# PIC.net
KiCad netlist of a schematic drawn in Altium Designer
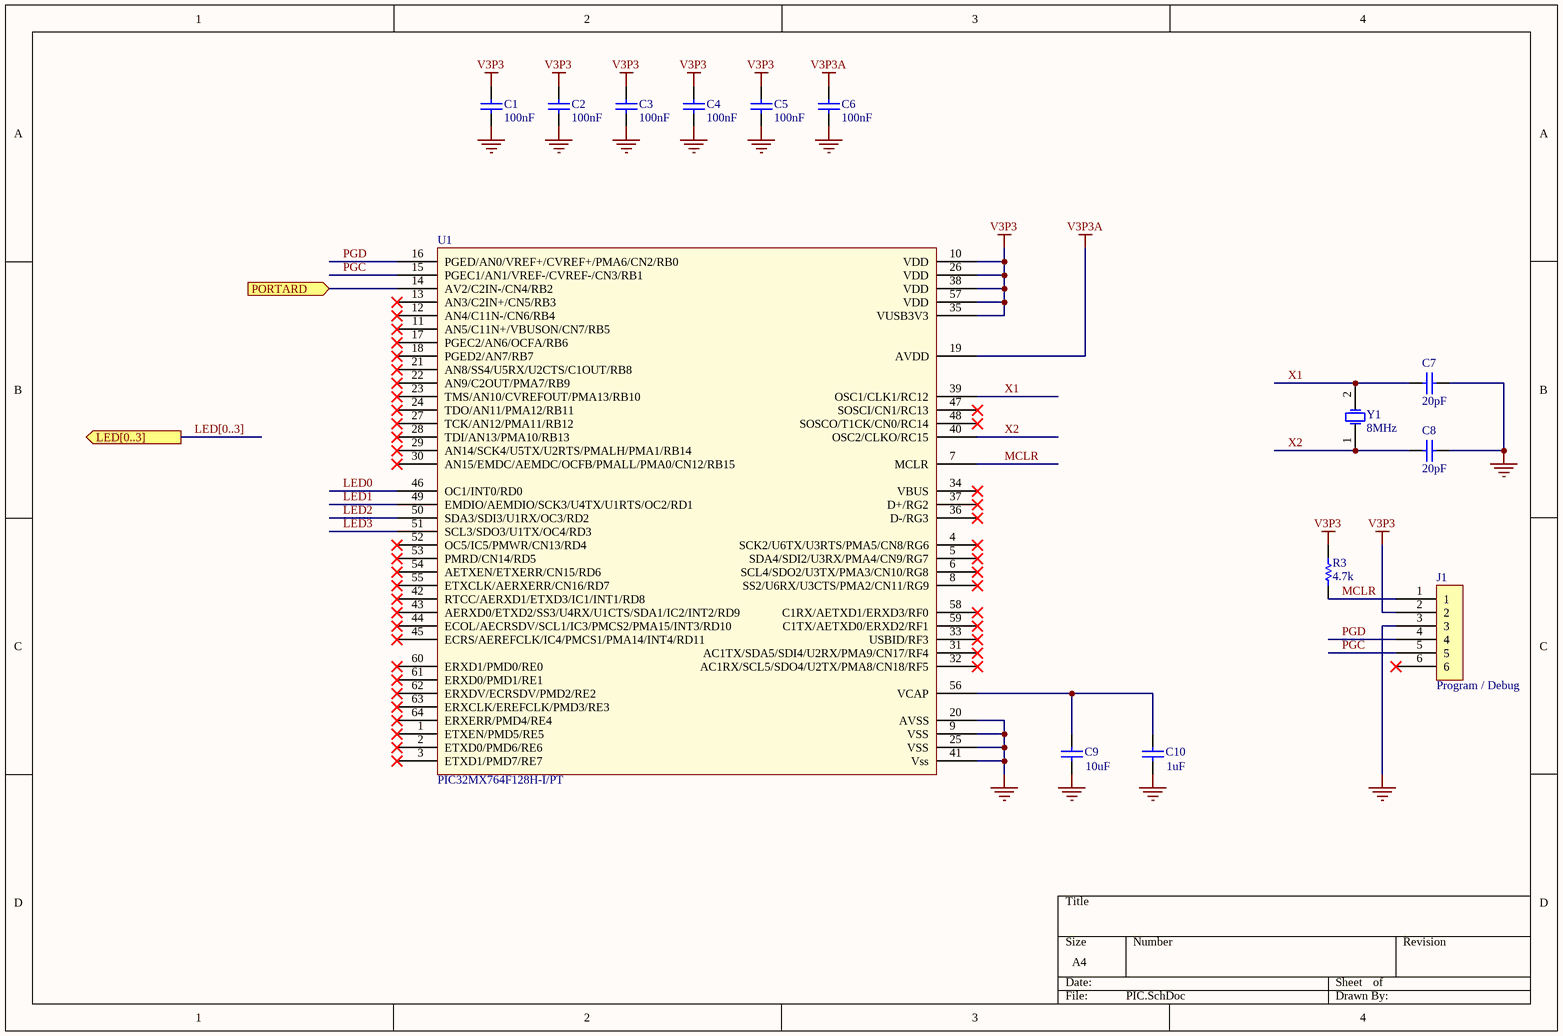
[diagram p0: PIC.SchDoc]

(export (version "E")
  (design (tool "Eeschema 10.0.6"))
  (components
    (comp (ref "C1")
      (value "100nF")
      (footprint "CAPC1608N")
      (description "Capacitor")
      (libsource (lib "Miscellaneous Devices") (part "Cap"))
    )
    (comp (ref "C2")
      (value "100nF")
      (footprint "CAPC1608N")
      (description "Capacitor")
      (libsource (lib "Miscellaneous Devices") (part "Cap"))
    )
    (comp (ref "C3")
      (value "100nF")
      (footprint "CAPC1608N")
      (description "Capacitor")
      (libsource (lib "Miscellaneous Devices") (part "Cap"))
    )
    (comp (ref "C4")
      (value "100nF")
      (footprint "CAPC1608N")
      (description "Capacitor")
      (libsource (lib "Miscellaneous Devices") (part "Cap"))
    )
    (comp (ref "C5")
      (value "100nF")
      (footprint "CAPC1608N")
      (description "Capacitor")
      (libsource (lib "Miscellaneous Devices") (part "Cap"))
    )
    (comp (ref "C6")
      (value "100nF")
      (footprint "CAPC1608N")
      (description "Capacitor")
      (libsource (lib "Miscellaneous Devices") (part "Cap"))
    )
    (comp (ref "C7")
      (value "20pF")
      (footprint "CAPC1608N")
      (description "Capacitor")
      (libsource (lib "Miscellaneous Devices") (part "Cap"))
    )
    (comp (ref "C8")
      (value "20pF")
      (footprint "CAPC1608N")
      (description "Capacitor")
      (libsource (lib "Miscellaneous Devices") (part "Cap"))
    )
    (comp (ref "C9")
      (value "10uF")
      (footprint "CAPC2012N")
      (description "Capacitor")
      (libsource (lib "Miscellaneous Devices") (part "Cap"))
    )
    (comp (ref "C10")
      (value "1uF")
      (footprint "CAPC1608N")
      (description "Capacitor")
      (libsource (lib "Miscellaneous Devices") (part "Cap"))
    )
    (comp (ref "J1")
      (value "Program / Debug")
      (footprint "RJ12_90")
      (libsource (lib "Schlib1") (part "Program / Debug"))
    )
    (comp (ref "R3")
      (value "4.7k")
      (footprint "RESC1608N")
      (description "Resistor")
      (libsource (lib "Miscellaneous Devices") (part "Res1"))
    )
    (comp (ref "U1")
      (value "PIC32MX764F128H-I/PT")
      (footprint "QFP50P1200X1200X120-64")
      (libsource (lib "Schlib1") (part "PIC32MX764F128H-I/PT"))
    )
    (comp (ref "Y1")
      (value "8MHz")
      (footprint "HC49/4H SMX Crystal")
      (description "Crystal Oscillator")
      (libsource (lib "Miscellaneous Devices") (part "XTAL"))
    )
  )
  (nets
    (net (code "1") (name "/LED0") (class "Default")
      (node (ref "U1") (pin "46") (pinfunction "OC1/INT0/RD0_46") (pintype "passive"))
    )
    (net (code "2") (name "/LED1") (class "Default")
      (node (ref "U1") (pin "49") (pinfunction "EMDIO/AEMDIO/SCK3/U4TX/U1RTS/OC2/RD1_49") (pintype "passive"))
    )
    (net (code "3") (name "/LED2") (class "Default")
      (node (ref "U1") (pin "50") (pinfunction "SDA3/SDI3/U1RX/OC3/RD2_50") (pintype "passive"))
    )
    (net (code "4") (name "/LED3") (class "Default")
      (node (ref "U1") (pin "51") (pinfunction "SCL3/SDO3/U1TX/OC4/RD3_51") (pintype "passive"))
    )
    (net (code "6") (name "/MCLR") (class "Default")
      (node (ref "J1") (pin "1") (pinfunction "1_1") (pintype "passive"))
      (node (ref "R3") (pin "1") (pinfunction "1_1") (pintype "passive"))
      (node (ref "U1") (pin "7") (pinfunction "MCLR_7") (pintype "passive"))
    )
    (net (code "7") (name "/PGC") (class "Default")
      (node (ref "J1") (pin "5") (pinfunction "5_5") (pintype "passive"))
      (node (ref "U1") (pin "15") (pinfunction "PGEC1/AN1/VREF-/CVREF-/CN3/RB1_15") (pintype "passive"))
    )
    (net (code "8") (name "/PGD") (class "Default")
      (node (ref "J1") (pin "4") (pinfunction "4_4") (pintype "passive"))
      (node (ref "U1") (pin "16") (pinfunction "PGED/AN0/VREF+/CVREF+/PMA6/CN2/RB0_16") (pintype "passive"))
    )
    (net (code "9") (name "/PORTARD") (class "Default")
      (node (ref "U1") (pin "14") (pinfunction "AV2/C2IN-/CN4/RB2_14") (pintype "passive"))
    )
    (net (code "10") (name "/X1") (class "Default")
      (node (ref "C7") (pin "1") (pinfunction "1_1") (pintype "passive"))
      (node (ref "U1") (pin "39") (pinfunction "OSC1/CLK1/RC12_39") (pintype "passive"))
      (node (ref "Y1") (pin "2") (pinfunction "OSC2_2") (pintype "passive"))
    )
    (net (code "11") (name "/X2") (class "Default")
      (node (ref "C8") (pin "1") (pinfunction "1_1") (pintype "passive"))
      (node (ref "U1") (pin "40") (pinfunction "OSC2/CLKO/RC15_40") (pintype "passive"))
      (node (ref "Y1") (pin "1") (pinfunction "OSC1_1") (pintype "passive"))
    )
    (net (code "12") (name "GND") (class "Default")
      (node (ref "C1") (pin "1") (pinfunction "1_1") (pintype "passive"))
      (node (ref "C10") (pin "1") (pinfunction "1_1") (pintype "passive"))
      (node (ref "C2") (pin "1") (pinfunction "1_1") (pintype "passive"))
      (node (ref "C3") (pin "1") (pinfunction "1_1") (pintype "passive"))
      (node (ref "C4") (pin "1") (pinfunction "1_1") (pintype "passive"))
      (node (ref "C5") (pin "1") (pinfunction "1_1") (pintype "passive"))
      (node (ref "C6") (pin "1") (pinfunction "1_1") (pintype "passive"))
      (node (ref "C7") (pin "2") (pinfunction "2_2") (pintype "passive"))
      (node (ref "C8") (pin "2") (pinfunction "2_2") (pintype "passive"))
      (node (ref "C9") (pin "1") (pinfunction "1_1") (pintype "passive"))
      (node (ref "J1") (pin "3") (pinfunction "3_3") (pintype "passive"))
      (node (ref "U1") (pin "20") (pinfunction "AVSS_20") (pintype "passive"))
      (node (ref "U1") (pin "25") (pinfunction "VSS_25") (pintype "passive"))
      (node (ref "U1") (pin "41") (pinfunction "Vss_41") (pintype "passive"))
      (node (ref "U1") (pin "9") (pinfunction "VSS_9") (pintype "passive"))
    )
    (net (code "13") (name "Net-(U1-VCAP)") (class "Default")
      (node (ref "C10") (pin "2") (pinfunction "2_2") (pintype "passive"))
      (node (ref "C9") (pin "2") (pinfunction "2_2") (pintype "passive"))
      (node (ref "U1") (pin "56") (pinfunction "VCAP_56") (pintype "passive"))
    )
    (net (code "14") (name "V3P3") (class "Default")
      (node (ref "C1") (pin "2") (pinfunction "2_2") (pintype "passive"))
      (node (ref "C2") (pin "2") (pinfunction "2_2") (pintype "passive"))
      (node (ref "C3") (pin "2") (pinfunction "2_2") (pintype "passive"))
      (node (ref "C4") (pin "2") (pinfunction "2_2") (pintype "passive"))
      (node (ref "C5") (pin "2") (pinfunction "2_2") (pintype "passive"))
      (node (ref "J1") (pin "2") (pinfunction "2_2") (pintype "passive"))
      (node (ref "R3") (pin "2") (pinfunction "2_2") (pintype "passive"))
      (node (ref "U1") (pin "10") (pinfunction "VDD_10") (pintype "passive"))
      (node (ref "U1") (pin "26") (pinfunction "VDD_26") (pintype "passive"))
      (node (ref "U1") (pin "35") (pinfunction "VUSB3V3_35") (pintype "passive"))
      (node (ref "U1") (pin "38") (pinfunction "VDD_38") (pintype "passive"))
      (node (ref "U1") (pin "57") (pinfunction "VDD_57") (pintype "passive"))
    )
    (net (code "15") (name "V3P3A") (class "Default")
      (node (ref "C6") (pin "2") (pinfunction "2_2") (pintype "passive"))
      (node (ref "U1") (pin "19") (pinfunction "AVDD_19") (pintype "passive"))
    )
    (net (code "16") (name "unconnected-(J1-Pad6)") (class "Default")
      (node (ref "J1") (pin "6") (pinfunction "6_6") (pintype "passive+no_connect"))
    )
    (net (code "17") (name "unconnected-(U1-AC1RX{slash}SCL5{slash}SDO4{slash}U2TX{slash}PMA8{slash}CN18{slash}RF5-Pad32)") (class "Default")
      (node (ref "U1") (pin "32") (pinfunction "AC1RX/SCL5/SDO4/U2TX/PMA8/CN18/RF5_32") (pintype "passive+no_connect"))
    )
    (net (code "18") (name "unconnected-(U1-AC1TX{slash}SDA5{slash}SDI4{slash}U2RX{slash}PMA9{slash}CN17{slash}RF4-Pad31)") (class "Default")
      (node (ref "U1") (pin "31") (pinfunction "AC1TX/SDA5/SDI4/U2RX/PMA9/CN17/RF4_31") (pintype "passive+no_connect"))
    )
    (net (code "19") (name "unconnected-(U1-AERXD0{slash}ETXD2{slash}SS3{slash}U4RX{slash}U1CTS{slash}SDA1{slash}IC2{slash}INT2{slash}RD9-Pad43)") (class "Default")
      (node (ref "U1") (pin "43") (pinfunction "AERXD0/ETXD2/SS3/U4RX/U1CTS/SDA1/IC2/INT2/RD9_43") (pintype "passive+no_connect"))
    )
    (net (code "20") (name "unconnected-(U1-AETXEN{slash}ETXERR{slash}CN15{slash}RD6-Pad54)") (class "Default")
      (node (ref "U1") (pin "54") (pinfunction "AETXEN/ETXERR/CN15/RD6_54") (pintype "passive+no_connect"))
    )
    (net (code "21") (name "unconnected-(U1-AN3{slash}C2IN+{slash}CN5{slash}RB3-Pad13)") (class "Default")
      (node (ref "U1") (pin "13") (pinfunction "AN3/C2IN+/CN5/RB3_13") (pintype "passive+no_connect"))
    )
    (net (code "22") (name "unconnected-(U1-AN4{slash}C11N-{slash}CN6{slash}RB4-Pad12)") (class "Default")
      (node (ref "U1") (pin "12") (pinfunction "AN4/C11N-/CN6/RB4_12") (pintype "passive+no_connect"))
    )
    (net (code "23") (name "unconnected-(U1-AN5{slash}C11N+{slash}VBUSON{slash}CN7{slash}RB5-Pad11)") (class "Default")
      (node (ref "U1") (pin "11") (pinfunction "AN5/C11N+/VBUSON/CN7/RB5_11") (pintype "passive+no_connect"))
    )
    (net (code "24") (name "unconnected-(U1-AN8{slash}SS4{slash}U5RX{slash}U2CTS{slash}C1OUT{slash}RB8-Pad21)") (class "Default")
      (node (ref "U1") (pin "21") (pinfunction "AN8/SS4/U5RX/U2CTS/C1OUT/RB8_21") (pintype "passive+no_connect"))
    )
    (net (code "25") (name "unconnected-(U1-AN9{slash}C2OUT{slash}PMA7{slash}RB9-Pad22)") (class "Default")
      (node (ref "U1") (pin "22") (pinfunction "AN9/C2OUT/PMA7/RB9_22") (pintype "passive+no_connect"))
    )
    (net (code "26") (name "unconnected-(U1-AN14{slash}SCK4{slash}U5TX{slash}U2RTS{slash}PMALH{slash}PMA1{slash}RB14-Pad29)") (class "Default")
      (node (ref "U1") (pin "29") (pinfunction "AN14/SCK4/U5TX/U2RTS/PMALH/PMA1/RB14_29") (pintype "passive+no_connect"))
    )
    (net (code "27") (name "unconnected-(U1-AN15{slash}EMDC{slash}AEMDC{slash}OCFB{slash}PMALL{slash}PMA0{slash}CN12{slash}RB15-Pad30)") (class "Default")
      (node (ref "U1") (pin "30") (pinfunction "AN15/EMDC/AEMDC/OCFB/PMALL/PMA0/CN12/RB15_30") (pintype "passive+no_connect"))
    )
    (net (code "28") (name "unconnected-(U1-C1RX{slash}AETXD1{slash}ERXD3{slash}RF0-Pad58)") (class "Default")
      (node (ref "U1") (pin "58") (pinfunction "C1RX/AETXD1/ERXD3/RF0_58") (pintype "passive+no_connect"))
    )
    (net (code "29") (name "unconnected-(U1-C1TX{slash}AETXD0{slash}ERXD2{slash}RF1-Pad59)") (class "Default")
      (node (ref "U1") (pin "59") (pinfunction "C1TX/AETXD0/ERXD2/RF1_59") (pintype "passive+no_connect"))
    )
    (net (code "30") (name "unconnected-(U1-D+{slash}RG2-Pad37)") (class "Default")
      (node (ref "U1") (pin "37") (pinfunction "D+/RG2_37") (pintype "passive+no_connect"))
    )
    (net (code "31") (name "unconnected-(U1-D-{slash}RG3-Pad36)") (class "Default")
      (node (ref "U1") (pin "36") (pinfunction "D-/RG3_36") (pintype "passive+no_connect"))
    )
    (net (code "32") (name "unconnected-(U1-ECOL{slash}AECRSDV{slash}SCL1{slash}IC3{slash}PMCS2{slash}PMA15{slash}INT3{slash}RD10-Pad44)") (class "Default")
      (node (ref "U1") (pin "44") (pinfunction "ECOL/AECRSDV/SCL1/IC3/PMCS2/PMA15/INT3/RD10_44") (pintype "passive+no_connect"))
    )
    (net (code "33") (name "unconnected-(U1-ECRS{slash}AEREFCLK{slash}IC4{slash}PMCS1{slash}PMA14{slash}INT4{slash}RD11-Pad45)") (class "Default")
      (node (ref "U1") (pin "45") (pinfunction "ECRS/AEREFCLK/IC4/PMCS1/PMA14/INT4/RD11_45") (pintype "passive+no_connect"))
    )
    (net (code "34") (name "unconnected-(U1-ERXCLK{slash}EREFCLK{slash}PMD3{slash}RE3-Pad63)") (class "Default")
      (node (ref "U1") (pin "63") (pinfunction "ERXCLK/EREFCLK/PMD3/RE3_63") (pintype "passive+no_connect"))
    )
    (net (code "35") (name "unconnected-(U1-ERXD0{slash}PMD1{slash}RE1-Pad61)") (class "Default")
      (node (ref "U1") (pin "61") (pinfunction "ERXD0/PMD1/RE1_61") (pintype "passive+no_connect"))
    )
    (net (code "36") (name "unconnected-(U1-ERXD1{slash}PMD0{slash}RE0-Pad60)") (class "Default")
      (node (ref "U1") (pin "60") (pinfunction "ERXD1/PMD0/RE0_60") (pintype "passive+no_connect"))
    )
    (net (code "37") (name "unconnected-(U1-ERXDV{slash}ECRSDV{slash}PMD2{slash}RE2-Pad62)") (class "Default")
      (node (ref "U1") (pin "62") (pinfunction "ERXDV/ECRSDV/PMD2/RE2_62") (pintype "passive+no_connect"))
    )
    (net (code "38") (name "unconnected-(U1-ERXERR{slash}PMD4{slash}RE4-Pad64)") (class "Default")
      (node (ref "U1") (pin "64") (pinfunction "ERXERR/PMD4/RE4_64") (pintype "passive+no_connect"))
    )
    (net (code "39") (name "unconnected-(U1-ETXCLK{slash}AERXERR{slash}CN16{slash}RD7-Pad55)") (class "Default")
      (node (ref "U1") (pin "55") (pinfunction "ETXCLK/AERXERR/CN16/RD7_55") (pintype "passive+no_connect"))
    )
    (net (code "40") (name "unconnected-(U1-ETXD0{slash}PMD6{slash}RE6-Pad2)") (class "Default")
      (node (ref "U1") (pin "2") (pinfunction "ETXD0/PMD6/RE6_2") (pintype "passive+no_connect"))
    )
    (net (code "41") (name "unconnected-(U1-ETXD1{slash}PMD7{slash}RE7-Pad3)") (class "Default")
      (node (ref "U1") (pin "3") (pinfunction "ETXD1/PMD7/RE7_3") (pintype "passive+no_connect"))
    )
    (net (code "42") (name "unconnected-(U1-ETXEN{slash}PMD5{slash}RE5-Pad1)") (class "Default")
      (node (ref "U1") (pin "1") (pinfunction "ETXEN/PMD5/RE5_1") (pintype "passive+no_connect"))
    )
    (net (code "43") (name "unconnected-(U1-OC5{slash}IC5{slash}PMWR{slash}CN13{slash}RD4-Pad52)") (class "Default")
      (node (ref "U1") (pin "52") (pinfunction "OC5/IC5/PMWR/CN13/RD4_52") (pintype "passive+no_connect"))
    )
    (net (code "44") (name "unconnected-(U1-PGEC2{slash}AN6{slash}OCFA{slash}RB6-Pad17)") (class "Default")
      (node (ref "U1") (pin "17") (pinfunction "PGEC2/AN6/OCFA/RB6_17") (pintype "passive+no_connect"))
    )
    (net (code "45") (name "unconnected-(U1-PGED2{slash}AN7{slash}RB7-Pad18)") (class "Default")
      (node (ref "U1") (pin "18") (pinfunction "PGED2/AN7/RB7_18") (pintype "passive+no_connect"))
    )
    (net (code "46") (name "unconnected-(U1-PMRD{slash}CN14{slash}RD5-Pad53)") (class "Default")
      (node (ref "U1") (pin "53") (pinfunction "PMRD/CN14/RD5_53") (pintype "passive+no_connect"))
    )
    (net (code "47") (name "unconnected-(U1-RTCC{slash}AERXD1{slash}ETXD3{slash}IC1{slash}INT1{slash}RD8-Pad42)") (class "Default")
      (node (ref "U1") (pin "42") (pinfunction "RTCC/AERXD1/ETXD3/IC1/INT1/RD8_42") (pintype "passive+no_connect"))
    )
    (net (code "48") (name "unconnected-(U1-SCK2{slash}U6TX{slash}U3RTS{slash}PMA5{slash}CN8{slash}RG6-Pad4)") (class "Default")
      (node (ref "U1") (pin "4") (pinfunction "SCK2/U6TX/U3RTS/PMA5/CN8/RG6_4") (pintype "passive+no_connect"))
    )
    (net (code "49") (name "unconnected-(U1-SCL4{slash}SDO2{slash}U3TX{slash}PMA3{slash}CN10{slash}RG8-Pad6)") (class "Default")
      (node (ref "U1") (pin "6") (pinfunction "SCL4/SDO2/U3TX/PMA3/CN10/RG8_6") (pintype "passive+no_connect"))
    )
    (net (code "50") (name "unconnected-(U1-SDA4{slash}SDI2{slash}U3RX{slash}PMA4{slash}CN9{slash}RG7-Pad5)") (class "Default")
      (node (ref "U1") (pin "5") (pinfunction "SDA4/SDI2/U3RX/PMA4/CN9/RG7_5") (pintype "passive+no_connect"))
    )
    (net (code "51") (name "unconnected-(U1-SOSCI{slash}CN1{slash}RC13-Pad47)") (class "Default")
      (node (ref "U1") (pin "47") (pinfunction "SOSCI/CN1/RC13_47") (pintype "passive+no_connect"))
    )
    (net (code "52") (name "unconnected-(U1-SOSCO{slash}T1CK{slash}CN0{slash}RC14-Pad48)") (class "Default")
      (node (ref "U1") (pin "48") (pinfunction "SOSCO/T1CK/CN0/RC14_48") (pintype "passive+no_connect"))
    )
    (net (code "53") (name "unconnected-(U1-SS2{slash}U6RX{slash}U3CTS{slash}PMA2{slash}CN11{slash}RG9-Pad8)") (class "Default")
      (node (ref "U1") (pin "8") (pinfunction "SS2/U6RX/U3CTS/PMA2/CN11/RG9_8") (pintype "passive+no_connect"))
    )
    (net (code "54") (name "unconnected-(U1-TCK{slash}AN12{slash}PMA11{slash}RB12-Pad27)") (class "Default")
      (node (ref "U1") (pin "27") (pinfunction "TCK/AN12/PMA11/RB12_27") (pintype "passive+no_connect"))
    )
    (net (code "55") (name "unconnected-(U1-TDI{slash}AN13{slash}PMA10{slash}RB13-Pad28)") (class "Default")
      (node (ref "U1") (pin "28") (pinfunction "TDI/AN13/PMA10/RB13_28") (pintype "passive+no_connect"))
    )
    (net (code "56") (name "unconnected-(U1-TDO{slash}AN11{slash}PMA12{slash}RB11-Pad24)") (class "Default")
      (node (ref "U1") (pin "24") (pinfunction "TDO/AN11/PMA12/RB11_24") (pintype "passive+no_connect"))
    )
    (net (code "57") (name "unconnected-(U1-TMS{slash}AN10{slash}CVREFOUT{slash}PMA13{slash}RB10-Pad23)") (class "Default")
      (node (ref "U1") (pin "23") (pinfunction "TMS/AN10/CVREFOUT/PMA13/RB10_23") (pintype "passive+no_connect"))
    )
    (net (code "58") (name "unconnected-(U1-USBID{slash}RF3-Pad33)") (class "Default")
      (node (ref "U1") (pin "33") (pinfunction "USBID/RF3_33") (pintype "passive+no_connect"))
    )
    (net (code "59") (name "unconnected-(U1-VBUS-Pad34)") (class "Default")
      (node (ref "U1") (pin "34") (pinfunction "VBUS_34") (pintype "passive+no_connect"))
    )
  )
)
